# Solar_Tracker_without_using_ATmega328P.net
KiCad netlist of a schematic drawn in EAGLE
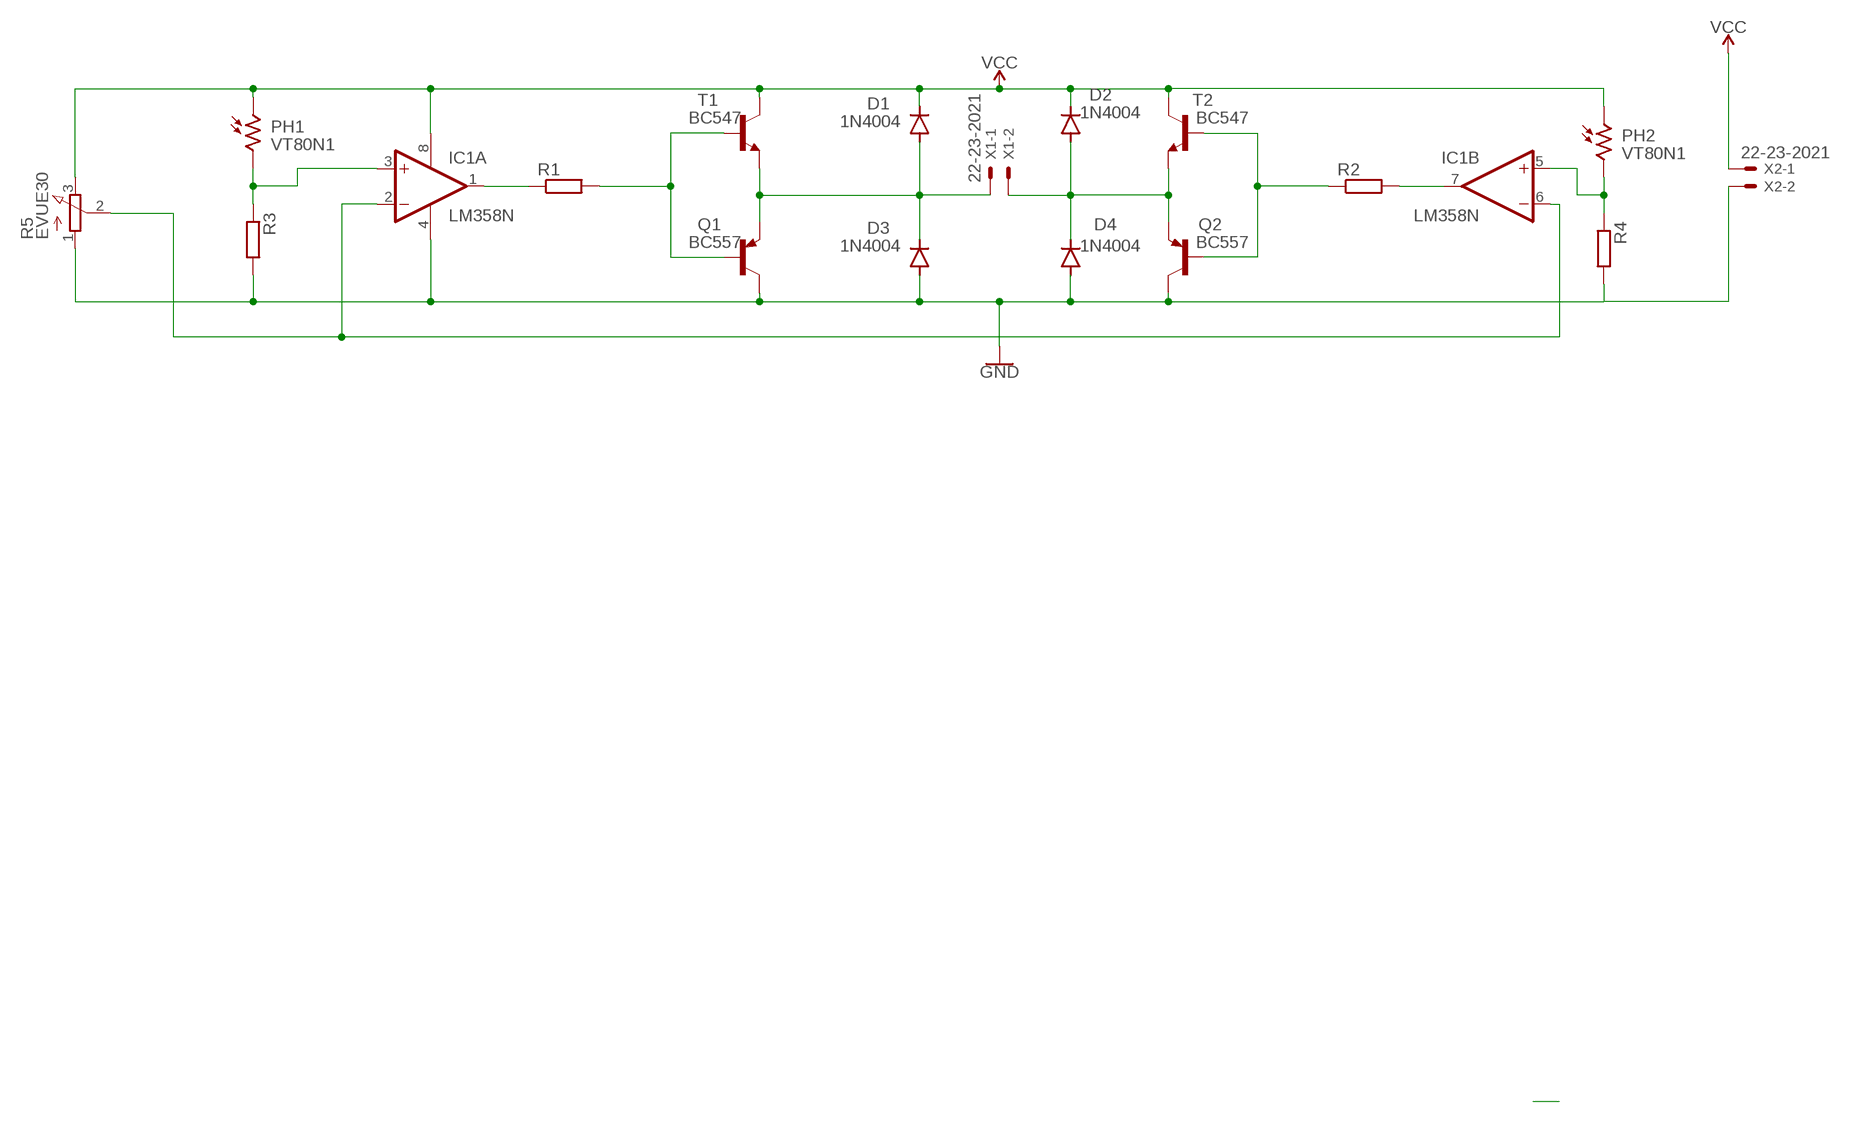
[diagram p0: schematic, sheet 1]

(export (version "E")
  (design (tool "Eeschema 10.0.6"))
  (components
    (comp (ref "D1")
      (value "1N4004")
      (footprint "eagle-import:DO41-10")
      (libsource (lib "eagle-import") (part "1N4004"))
    )
    (comp (ref "D2")
      (value "1N4004")
      (footprint "eagle-import:DO41-10")
      (libsource (lib "eagle-import") (part "1N4004"))
    )
    (comp (ref "D3")
      (value "1N4004")
      (footprint "eagle-import:DO41-10")
      (libsource (lib "eagle-import") (part "1N4004"))
    )
    (comp (ref "D4")
      (value "1N4004")
      (footprint "eagle-import:DO41-10")
      (libsource (lib "eagle-import") (part "1N4004"))
    )
    (comp (ref "IC1")
      (value "LM358N")
      (footprint "eagle-import:DIL08")
      (libsource (lib "eagle-import") (part "LM358N"))
    )
    (comp (ref "PH1")
      (value "VT80N1")
      (footprint "eagle-import:VT800")
      (libsource (lib "eagle-import") (part "VT80N1"))
    )
    (comp (ref "PH2")
      (value "VT80N1")
      (footprint "eagle-import:VT800")
      (libsource (lib "eagle-import") (part "VT80N1"))
    )
    (comp (ref "Q1")
      (value "BC557")
      (footprint "eagle-import:TO92")
      (libsource (lib "eagle-import") (part "BC557"))
    )
    (comp (ref "Q2")
      (value "BC557")
      (footprint "eagle-import:TO92")
      (libsource (lib "eagle-import") (part "BC557"))
    )
    (comp (ref "R1")
      (value "R-EU_0204/7")
      (footprint "eagle-import:0204_7")
      (libsource (lib "eagle-import") (part "R-EU_0204/7"))
    )
    (comp (ref "R2")
      (value "R-EU_0204/7")
      (footprint "eagle-import:0204_7")
      (libsource (lib "eagle-import") (part "R-EU_0204/7"))
    )
    (comp (ref "R3")
      (value "R-EU_0204/7")
      (footprint "eagle-import:0204_7")
      (libsource (lib "eagle-import") (part "R-EU_0204/7"))
    )
    (comp (ref "R4")
      (value "R-EU_0204/7")
      (footprint "eagle-import:0204_7")
      (libsource (lib "eagle-import") (part "R-EU_0204/7"))
    )
    (comp (ref "R5")
      (value "EVUE30")
      (footprint "eagle-import:EVUE")
      (libsource (lib "eagle-import") (part "EVUE30"))
    )
    (comp (ref "T1")
      (value "BC547")
      (footprint "eagle-import:TO92")
      (libsource (lib "eagle-import") (part "BC547"))
    )
    (comp (ref "T2")
      (value "BC547")
      (footprint "eagle-import:TO92")
      (libsource (lib "eagle-import") (part "BC547"))
    )
    (comp (ref "X1")
      (value "22-23-2021")
      (footprint "eagle-import:22-23-2021")
      (fields (field (name "MF") "MOLEX"))
      (libsource (lib "eagle-import") (part "22-23-2021"))
    )
    (comp (ref "X2")
      (value "22-23-2021")
      (footprint "eagle-import:22-23-2021")
      (fields (field (name "MF") "MOLEX"))
      (libsource (lib "eagle-import") (part "22-23-2021"))
    )
  )
  (nets
    (net (code "1") (name "GND") (class "Default")
      (node (ref "D3") (pin "A") (pinfunction "A_A") (pintype "passive"))
      (node (ref "D4") (pin "A") (pinfunction "A_A") (pintype "passive"))
      (node (ref "IC1") (pin "4") (pinfunction "V-_4") (pintype "power_in"))
      (node (ref "Q1") (pin "3") (pinfunction "C_3") (pintype "passive"))
      (node (ref "Q2") (pin "3") (pinfunction "C_3") (pintype "passive"))
      (node (ref "R3") (pin "2") (pinfunction "2_2") (pintype "passive"))
      (node (ref "R4") (pin "2") (pinfunction "2_2") (pintype "passive"))
      (node (ref "R5") (pin "1") (pinfunction "A_1") (pintype "passive"))
      (node (ref "X2") (pin "2") (pinfunction "S_2") (pintype "passive"))
    )
    (net (code "2") (name "Net-(IC1A-+IN)") (class "Default")
      (node (ref "IC1") (pin "3") (pinfunction "+IN_3") (pintype "input"))
      (node (ref "PH1") (pin "2") (pinfunction "2_2") (pintype "passive"))
      (node (ref "R3") (pin "1") (pinfunction "1_1") (pintype "passive"))
    )
    (net (code "3") (name "Net-(IC1A--IN)") (class "Default")
      (node (ref "IC1") (pin "2") (pinfunction "-IN_2") (pintype "input"))
      (node (ref "IC1") (pin "6") (pinfunction "-IN_6") (pintype "input"))
      (node (ref "R5") (pin "2") (pinfunction "S_2") (pintype "passive"))
    )
    (net (code "4") (name "Net-(IC1A-OUT)") (class "Default")
      (node (ref "IC1") (pin "1") (pinfunction "OUT_1") (pintype "output"))
      (node (ref "R1") (pin "1") (pinfunction "1_1") (pintype "passive"))
    )
    (net (code "5") (name "Net-(IC1B-+IN)") (class "Default")
      (node (ref "IC1") (pin "5") (pinfunction "+IN_5") (pintype "input"))
      (node (ref "PH2") (pin "2") (pinfunction "2_2") (pintype "passive"))
      (node (ref "R4") (pin "1") (pinfunction "1_1") (pintype "passive"))
    )
    (net (code "6") (name "Net-(IC1B-OUT)") (class "Default")
      (node (ref "IC1") (pin "7") (pinfunction "OUT_7") (pintype "output"))
      (node (ref "R2") (pin "2") (pinfunction "2_2") (pintype "passive"))
    )
    (net (code "7") (name "Net-(Q1-B)") (class "Default")
      (node (ref "Q1") (pin "2") (pinfunction "B_2") (pintype "passive"))
      (node (ref "R1") (pin "2") (pinfunction "2_2") (pintype "passive"))
      (node (ref "T1") (pin "2") (pinfunction "B_2") (pintype "passive"))
    )
    (net (code "8") (name "Net-(Q1-E)") (class "Default")
      (node (ref "D1") (pin "A") (pinfunction "A_A") (pintype "passive"))
      (node (ref "D3") (pin "C") (pinfunction "C_C") (pintype "passive"))
      (node (ref "Q1") (pin "1") (pinfunction "E_1") (pintype "passive"))
      (node (ref "T1") (pin "1") (pinfunction "E_1") (pintype "passive"))
      (node (ref "X1") (pin "1") (pinfunction "S_1") (pintype "passive"))
    )
    (net (code "9") (name "Net-(Q2-B)") (class "Default")
      (node (ref "Q2") (pin "2") (pinfunction "B_2") (pintype "passive"))
      (node (ref "R2") (pin "1") (pinfunction "1_1") (pintype "passive"))
      (node (ref "T2") (pin "2") (pinfunction "B_2") (pintype "passive"))
    )
    (net (code "10") (name "Net-(Q2-E)") (class "Default")
      (node (ref "D2") (pin "A") (pinfunction "A_A") (pintype "passive"))
      (node (ref "D4") (pin "C") (pinfunction "C_C") (pintype "passive"))
      (node (ref "Q2") (pin "1") (pinfunction "E_1") (pintype "passive"))
      (node (ref "T2") (pin "1") (pinfunction "E_1") (pintype "passive"))
      (node (ref "X1") (pin "2") (pinfunction "S_2") (pintype "passive"))
    )
    (net (code "11") (name "VCC") (class "Default")
      (node (ref "D1") (pin "C") (pinfunction "C_C") (pintype "passive"))
      (node (ref "D2") (pin "C") (pinfunction "C_C") (pintype "passive"))
      (node (ref "IC1") (pin "8") (pinfunction "V+_8") (pintype "power_in"))
      (node (ref "PH1") (pin "1") (pinfunction "1_1") (pintype "passive"))
      (node (ref "PH2") (pin "1") (pinfunction "1_1") (pintype "passive"))
      (node (ref "R5") (pin "3") (pinfunction "E_3") (pintype "passive"))
      (node (ref "T1") (pin "3") (pinfunction "C_3") (pintype "passive"))
      (node (ref "T2") (pin "3") (pinfunction "C_3") (pintype "passive"))
      (node (ref "X2") (pin "1") (pinfunction "S_1") (pintype "passive"))
    )
  )
)
